# WiFiChristmasStar.net
KiCad netlist of a schematic drawn in EAGLE
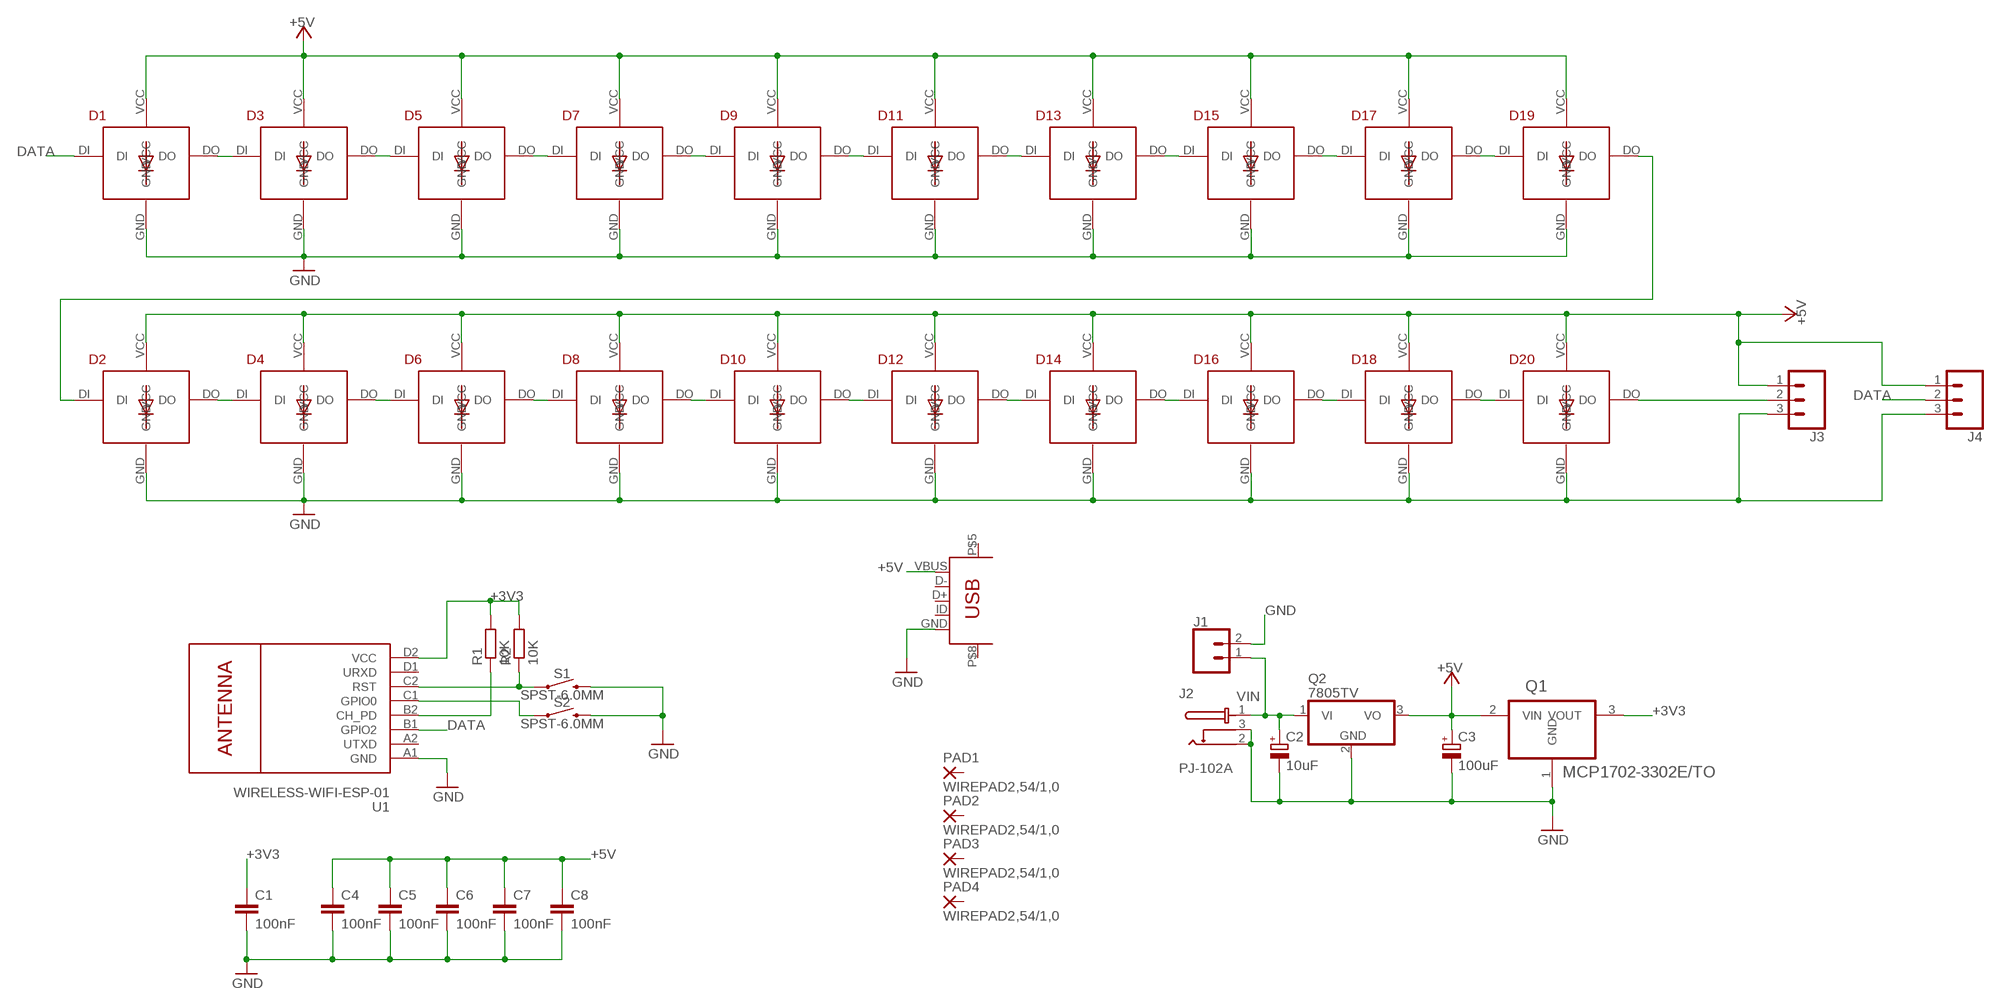
[diagram p0: schematic, sheet 1]

(export (version "E")
  (design (tool "Eeschema 10.0.6"))
  (components
    (comp (ref "C1")
      (value "100nF")
      (footprint "eagle-import:C025-025X050")
      (libsource (lib "eagle-import") (part "C-EU025-025X050"))
    )
    (comp (ref "C2")
      (value "10uF")
      (footprint "eagle-import:E2,5-6")
      (libsource (lib "eagle-import") (part "CPOL-EUE2.5-6"))
    )
    (comp (ref "C3")
      (value "100uF")
      (footprint "eagle-import:E2,5-6")
      (libsource (lib "eagle-import") (part "CPOL-EUE2.5-6"))
    )
    (comp (ref "C4")
      (value "100nF")
      (footprint "eagle-import:C025-025X050")
      (libsource (lib "eagle-import") (part "C-EU025-025X050"))
    )
    (comp (ref "C5")
      (value "100nF")
      (footprint "eagle-import:C025-025X050")
      (libsource (lib "eagle-import") (part "C-EU025-025X050"))
    )
    (comp (ref "C6")
      (value "100nF")
      (footprint "eagle-import:C025-025X050")
      (libsource (lib "eagle-import") (part "C-EU025-025X050"))
    )
    (comp (ref "C7")
      (value "100nF")
      (footprint "eagle-import:C025-025X050")
      (libsource (lib "eagle-import") (part "C-EU025-025X050"))
    )
    (comp (ref "C8")
      (value "100nF")
      (footprint "eagle-import:C025-025X050")
      (libsource (lib "eagle-import") (part "C-EU025-025X050"))
    )
    (comp (ref "CON1")
      (value "MOLEX-548190519-MICROUSB")
      (footprint "eagle-import:MOLEX-548190519")
      (libsource (lib "eagle-import") (part "MOLEX-548190519-MICROUSB"))
    )
    (comp (ref "D1")
      (value "APA-106")
      (footprint "eagle-import:LED5MMRGB")
      (libsource (lib "eagle-import") (part "APA-106"))
    )
    (comp (ref "D2")
      (value "APA-106")
      (footprint "eagle-import:LED5MMRGB")
      (libsource (lib "eagle-import") (part "APA-106"))
    )
    (comp (ref "D3")
      (value "APA-106")
      (footprint "eagle-import:LED5MMRGB")
      (libsource (lib "eagle-import") (part "APA-106"))
    )
    (comp (ref "D4")
      (value "APA-106")
      (footprint "eagle-import:LED5MMRGB")
      (libsource (lib "eagle-import") (part "APA-106"))
    )
    (comp (ref "D5")
      (value "APA-106")
      (footprint "eagle-import:LED5MMRGB")
      (libsource (lib "eagle-import") (part "APA-106"))
    )
    (comp (ref "D6")
      (value "APA-106")
      (footprint "eagle-import:LED5MMRGB")
      (libsource (lib "eagle-import") (part "APA-106"))
    )
    (comp (ref "D7")
      (value "APA-106")
      (footprint "eagle-import:LED5MMRGB")
      (libsource (lib "eagle-import") (part "APA-106"))
    )
    (comp (ref "D8")
      (value "APA-106")
      (footprint "eagle-import:LED5MMRGB")
      (libsource (lib "eagle-import") (part "APA-106"))
    )
    (comp (ref "D9")
      (value "APA-106")
      (footprint "eagle-import:LED5MMRGB")
      (libsource (lib "eagle-import") (part "APA-106"))
    )
    (comp (ref "D10")
      (value "APA-106")
      (footprint "eagle-import:LED5MMRGB")
      (libsource (lib "eagle-import") (part "APA-106"))
    )
    (comp (ref "D11")
      (value "APA-106")
      (footprint "eagle-import:LED5MMRGB")
      (libsource (lib "eagle-import") (part "APA-106"))
    )
    (comp (ref "D12")
      (value "APA-106")
      (footprint "eagle-import:LED5MMRGB")
      (libsource (lib "eagle-import") (part "APA-106"))
    )
    (comp (ref "D13")
      (value "APA-106")
      (footprint "eagle-import:LED5MMRGB")
      (libsource (lib "eagle-import") (part "APA-106"))
    )
    (comp (ref "D14")
      (value "APA-106")
      (footprint "eagle-import:LED5MMRGB")
      (libsource (lib "eagle-import") (part "APA-106"))
    )
    (comp (ref "D15")
      (value "APA-106")
      (footprint "eagle-import:LED5MMRGB")
      (libsource (lib "eagle-import") (part "APA-106"))
    )
    (comp (ref "D16")
      (value "APA-106")
      (footprint "eagle-import:LED5MMRGB")
      (libsource (lib "eagle-import") (part "APA-106"))
    )
    (comp (ref "D17")
      (value "APA-106")
      (footprint "eagle-import:LED5MMRGB")
      (libsource (lib "eagle-import") (part "APA-106"))
    )
    (comp (ref "D18")
      (value "APA-106")
      (footprint "eagle-import:LED5MMRGB")
      (libsource (lib "eagle-import") (part "APA-106"))
    )
    (comp (ref "D19")
      (value "APA-106")
      (footprint "eagle-import:LED5MMRGB")
      (libsource (lib "eagle-import") (part "APA-106"))
    )
    (comp (ref "D20")
      (value "APA-106")
      (footprint "eagle-import:LED5MMRGB")
      (libsource (lib "eagle-import") (part "APA-106"))
    )
    (comp (ref "J1")
      (value "CONN_023.5MM")
      (footprint "eagle-import:SCREWTERMINAL-3.5MM-2")
      (libsource (lib "eagle-import") (part "CONN_023.5MM"))
    )
    (comp (ref "J2")
      (value "PJ-102A")
      (footprint "eagle-import:CUI_PJ-102A")
      (fields (field (name "MANUFACTURER") "CUI inc") (field (name "MF") "CUI"))
      (libsource (lib "eagle-import") (part "PJ-102A"))
    )
    (comp (ref "J3")
      (value "CONN_03SCREW")
      (footprint "eagle-import:SCREWTERMINAL-3.5MM-3")
      (libsource (lib "eagle-import") (part "CONN_03SCREW"))
    )
    (comp (ref "J4")
      (value "CONN_03SCREW")
      (footprint "eagle-import:SCREWTERMINAL-3.5MM-3")
      (libsource (lib "eagle-import") (part "CONN_03SCREW"))
    )
    (comp (ref "PAD1")
      (value "WIREPAD2,54/1,0")
      (footprint "eagle-import:2,54_1,0")
      (libsource (lib "eagle-import") (part "WIREPAD2,54/1,0"))
    )
    (comp (ref "PAD2")
      (value "WIREPAD2,54/1,0")
      (footprint "eagle-import:2,54_1,0")
      (libsource (lib "eagle-import") (part "WIREPAD2,54/1,0"))
    )
    (comp (ref "PAD3")
      (value "WIREPAD2,54/1,0")
      (footprint "eagle-import:2,54_1,0")
      (libsource (lib "eagle-import") (part "WIREPAD2,54/1,0"))
    )
    (comp (ref "PAD4")
      (value "WIREPAD2,54/1,0")
      (footprint "eagle-import:2,54_1,0")
      (libsource (lib "eagle-import") (part "WIREPAD2,54/1,0"))
    )
    (comp (ref "Q1")
      (value "MCP1702-3302E/TO")
      (footprint "eagle-import:TO127P254X533-3")
      (libsource (lib "eagle-import") (part "MCP1702-3302E/TO"))
    )
    (comp (ref "Q2")
      (value "7805TV")
      (footprint "eagle-import:TO220V")
      (libsource (lib "eagle-import") (part "78TV05"))
    )
    (comp (ref "R1")
      (value "10K")
      (footprint "eagle-import:0204_7")
      (libsource (lib "eagle-import") (part "R-EU_0204/7"))
    )
    (comp (ref "R2")
      (value "10K")
      (footprint "eagle-import:0204_7")
      (libsource (lib "eagle-import") (part "R-EU_0204/7"))
    )
    (comp (ref "S1")
      (value "SPST-6.0MM")
      (footprint "eagle-import:TACTILE_SWITCH_PTH_6.0MM")
      (libsource (lib "eagle-import") (part "MOMENTARY-SWITCH-SPST-PTH-6.0MM"))
    )
    (comp (ref "S2")
      (value "SPST-6.0MM")
      (footprint "eagle-import:TACTILE_SWITCH_PTH_6.0MM")
      (libsource (lib "eagle-import") (part "MOMENTARY-SWITCH-SPST-PTH-6.0MM"))
    )
    (comp (ref "U1")
      (value "WIRELESS-WIFI-ESP-01")
      (footprint "eagle-import:WIRELESS-WIFI-ESP-01")
      (libsource (lib "eagle-import") (part "WIRELESS-WIFI-ESP-01"))
    )
  )
  (nets
    (net (code "1") (name "+5V") (class "Default")
      (node (ref "C3") (pin "+") (pinfunction "+_+") (pintype "passive"))
      (node (ref "C4") (pin "1") (pinfunction "1_1") (pintype "passive"))
      (node (ref "C5") (pin "1") (pinfunction "1_1") (pintype "passive"))
      (node (ref "C6") (pin "1") (pinfunction "1_1") (pintype "passive"))
      (node (ref "C7") (pin "1") (pinfunction "1_1") (pintype "passive"))
      (node (ref "C8") (pin "1") (pinfunction "1_1") (pintype "passive"))
      (node (ref "CON1") (pin "VBUS") (pinfunction "VBUS_VBUS") (pintype "bidirectional"))
      (node (ref "D1") (pin "VCC") (pinfunction "VCC_VCC") (pintype "bidirectional"))
      (node (ref "D10") (pin "VCC") (pinfunction "VCC_VCC") (pintype "bidirectional"))
      (node (ref "D11") (pin "VCC") (pinfunction "VCC_VCC") (pintype "bidirectional"))
      (node (ref "D12") (pin "VCC") (pinfunction "VCC_VCC") (pintype "bidirectional"))
      (node (ref "D13") (pin "VCC") (pinfunction "VCC_VCC") (pintype "bidirectional"))
      (node (ref "D14") (pin "VCC") (pinfunction "VCC_VCC") (pintype "bidirectional"))
      (node (ref "D15") (pin "VCC") (pinfunction "VCC_VCC") (pintype "bidirectional"))
      (node (ref "D16") (pin "VCC") (pinfunction "VCC_VCC") (pintype "bidirectional"))
      (node (ref "D17") (pin "VCC") (pinfunction "VCC_VCC") (pintype "bidirectional"))
      (node (ref "D18") (pin "VCC") (pinfunction "VCC_VCC") (pintype "bidirectional"))
      (node (ref "D19") (pin "VCC") (pinfunction "VCC_VCC") (pintype "bidirectional"))
      (node (ref "D2") (pin "VCC") (pinfunction "VCC_VCC") (pintype "bidirectional"))
      (node (ref "D20") (pin "VCC") (pinfunction "VCC_VCC") (pintype "bidirectional"))
      (node (ref "D3") (pin "VCC") (pinfunction "VCC_VCC") (pintype "bidirectional"))
      (node (ref "D4") (pin "VCC") (pinfunction "VCC_VCC") (pintype "bidirectional"))
      (node (ref "D5") (pin "VCC") (pinfunction "VCC_VCC") (pintype "bidirectional"))
      (node (ref "D6") (pin "VCC") (pinfunction "VCC_VCC") (pintype "bidirectional"))
      (node (ref "D7") (pin "VCC") (pinfunction "VCC_VCC") (pintype "bidirectional"))
      (node (ref "D8") (pin "VCC") (pinfunction "VCC_VCC") (pintype "bidirectional"))
      (node (ref "D9") (pin "VCC") (pinfunction "VCC_VCC") (pintype "bidirectional"))
      (node (ref "J3") (pin "1") (pinfunction "1_1") (pintype "passive"))
      (node (ref "J4") (pin "1") (pinfunction "1_1") (pintype "passive"))
      (node (ref "Q1") (pin "2") (pinfunction "VIN_2") (pintype "input"))
      (node (ref "Q2") (pin "3") (pinfunction "VO_3") (pintype "passive"))
    )
    (net (code "2") (name "/+3V3") (class "Default")
      (node (ref "C1") (pin "1") (pinfunction "1_1") (pintype "passive"))
      (node (ref "Q1") (pin "3") (pinfunction "VOUT_3") (pintype "output"))
      (node (ref "R1") (pin "2") (pinfunction "2_2") (pintype "passive"))
      (node (ref "R2") (pin "2") (pinfunction "2_2") (pintype "passive"))
      (node (ref "U1") (pin "D2") (pinfunction "VCC_D2") (pintype "power_in"))
    )
    (net (code "3") (name "/DATA") (class "Default")
      (node (ref "D1") (pin "DI") (pinfunction "DI_DI") (pintype "bidirectional"))
      (node (ref "J4") (pin "2") (pinfunction "2_2") (pintype "passive"))
      (node (ref "U1") (pin "B1") (pinfunction "GPIO2_B1") (pintype "bidirectional"))
    )
    (net (code "4") (name "/VIN") (class "Default")
      (node (ref "C2") (pin "+") (pinfunction "+_+") (pintype "passive"))
      (node (ref "J1") (pin "1") (pinfunction "1_1") (pintype "passive"))
      (node (ref "J2") (pin "1") (pinfunction "1_1") (pintype "power_in"))
      (node (ref "Q2") (pin "1") (pinfunction "VI_1") (pintype "input"))
    )
    (net (code "5") (name "GND") (class "Default")
      (node (ref "C1") (pin "2") (pinfunction "2_2") (pintype "passive"))
      (node (ref "C2") (pin "-") (pinfunction "-_-") (pintype "passive"))
      (node (ref "C3") (pin "-") (pinfunction "-_-") (pintype "passive"))
      (node (ref "C4") (pin "2") (pinfunction "2_2") (pintype "passive"))
      (node (ref "C5") (pin "2") (pinfunction "2_2") (pintype "passive"))
      (node (ref "C6") (pin "2") (pinfunction "2_2") (pintype "passive"))
      (node (ref "C7") (pin "2") (pinfunction "2_2") (pintype "passive"))
      (node (ref "C8") (pin "2") (pinfunction "2_2") (pintype "passive"))
      (node (ref "CON1") (pin "GND") (pinfunction "GND_GND") (pintype "bidirectional"))
      (node (ref "D1") (pin "GND") (pinfunction "GND_GND") (pintype "bidirectional"))
      (node (ref "D10") (pin "GND") (pinfunction "GND_GND") (pintype "bidirectional"))
      (node (ref "D11") (pin "GND") (pinfunction "GND_GND") (pintype "bidirectional"))
      (node (ref "D12") (pin "GND") (pinfunction "GND_GND") (pintype "bidirectional"))
      (node (ref "D13") (pin "GND") (pinfunction "GND_GND") (pintype "bidirectional"))
      (node (ref "D14") (pin "GND") (pinfunction "GND_GND") (pintype "bidirectional"))
      (node (ref "D15") (pin "GND") (pinfunction "GND_GND") (pintype "bidirectional"))
      (node (ref "D16") (pin "GND") (pinfunction "GND_GND") (pintype "bidirectional"))
      (node (ref "D17") (pin "GND") (pinfunction "GND_GND") (pintype "bidirectional"))
      (node (ref "D18") (pin "GND") (pinfunction "GND_GND") (pintype "bidirectional"))
      (node (ref "D19") (pin "GND") (pinfunction "GND_GND") (pintype "bidirectional"))
      (node (ref "D2") (pin "GND") (pinfunction "GND_GND") (pintype "bidirectional"))
      (node (ref "D20") (pin "GND") (pinfunction "GND_GND") (pintype "bidirectional"))
      (node (ref "D3") (pin "GND") (pinfunction "GND_GND") (pintype "bidirectional"))
      (node (ref "D4") (pin "GND") (pinfunction "GND_GND") (pintype "bidirectional"))
      (node (ref "D5") (pin "GND") (pinfunction "GND_GND") (pintype "bidirectional"))
      (node (ref "D6") (pin "GND") (pinfunction "GND_GND") (pintype "bidirectional"))
      (node (ref "D7") (pin "GND") (pinfunction "GND_GND") (pintype "bidirectional"))
      (node (ref "D8") (pin "GND") (pinfunction "GND_GND") (pintype "bidirectional"))
      (node (ref "D9") (pin "GND") (pinfunction "GND_GND") (pintype "bidirectional"))
      (node (ref "J1") (pin "2") (pinfunction "2_2") (pintype "passive"))
      (node (ref "J2") (pin "2") (pinfunction "2_2") (pintype "power_in"))
      (node (ref "J2") (pin "3") (pinfunction "3_3") (pintype "power_in"))
      (node (ref "J3") (pin "3") (pinfunction "3_3") (pintype "passive"))
      (node (ref "J4") (pin "3") (pinfunction "3_3") (pintype "passive"))
      (node (ref "Q1") (pin "1") (pinfunction "GND_1") (pintype "passive"))
      (node (ref "Q2") (pin "2") (pinfunction "GND_2") (pintype "passive"))
      (node (ref "S1") (pin "3") (pinfunction "2_3") (pintype "passive"))
      (node (ref "S2") (pin "3") (pinfunction "2_3") (pintype "passive"))
      (node (ref "U1") (pin "A1") (pinfunction "GND_A1") (pintype "power_in"))
    )
    (net (code "6") (name "Net-(D1-PadDO)") (class "Default")
      (node (ref "D1") (pin "DO") (pinfunction "DO_DO") (pintype "bidirectional"))
      (node (ref "D3") (pin "DI") (pinfunction "DI_DI") (pintype "bidirectional"))
    )
    (net (code "7") (name "Net-(D2-PadDO)") (class "Default")
      (node (ref "D2") (pin "DO") (pinfunction "DO_DO") (pintype "bidirectional"))
      (node (ref "D4") (pin "DI") (pinfunction "DI_DI") (pintype "bidirectional"))
    )
    (net (code "8") (name "Net-(D3-PadDO)") (class "Default")
      (node (ref "D3") (pin "DO") (pinfunction "DO_DO") (pintype "bidirectional"))
      (node (ref "D5") (pin "DI") (pinfunction "DI_DI") (pintype "bidirectional"))
    )
    (net (code "9") (name "Net-(D4-PadDO)") (class "Default")
      (node (ref "D4") (pin "DO") (pinfunction "DO_DO") (pintype "bidirectional"))
      (node (ref "D6") (pin "DI") (pinfunction "DI_DI") (pintype "bidirectional"))
    )
    (net (code "10") (name "Net-(D5-PadDO)") (class "Default")
      (node (ref "D5") (pin "DO") (pinfunction "DO_DO") (pintype "bidirectional"))
      (node (ref "D7") (pin "DI") (pinfunction "DI_DI") (pintype "bidirectional"))
    )
    (net (code "11") (name "Net-(D6-PadDO)") (class "Default")
      (node (ref "D6") (pin "DO") (pinfunction "DO_DO") (pintype "bidirectional"))
      (node (ref "D8") (pin "DI") (pinfunction "DI_DI") (pintype "bidirectional"))
    )
    (net (code "12") (name "Net-(D7-PadDO)") (class "Default")
      (node (ref "D7") (pin "DO") (pinfunction "DO_DO") (pintype "bidirectional"))
      (node (ref "D9") (pin "DI") (pinfunction "DI_DI") (pintype "bidirectional"))
    )
    (net (code "13") (name "Net-(D10-PadDI)") (class "Default")
      (node (ref "D10") (pin "DI") (pinfunction "DI_DI") (pintype "bidirectional"))
      (node (ref "D8") (pin "DO") (pinfunction "DO_DO") (pintype "bidirectional"))
    )
    (net (code "14") (name "Net-(D10-PadDO)") (class "Default")
      (node (ref "D10") (pin "DO") (pinfunction "DO_DO") (pintype "bidirectional"))
      (node (ref "D12") (pin "DI") (pinfunction "DI_DI") (pintype "bidirectional"))
    )
    (net (code "15") (name "Net-(D11-PadDI)") (class "Default")
      (node (ref "D11") (pin "DI") (pinfunction "DI_DI") (pintype "bidirectional"))
      (node (ref "D9") (pin "DO") (pinfunction "DO_DO") (pintype "bidirectional"))
    )
    (net (code "16") (name "Net-(D11-PadDO)") (class "Default")
      (node (ref "D11") (pin "DO") (pinfunction "DO_DO") (pintype "bidirectional"))
      (node (ref "D13") (pin "DI") (pinfunction "DI_DI") (pintype "bidirectional"))
    )
    (net (code "17") (name "Net-(D12-PadDO)") (class "Default")
      (node (ref "D12") (pin "DO") (pinfunction "DO_DO") (pintype "bidirectional"))
      (node (ref "D14") (pin "DI") (pinfunction "DI_DI") (pintype "bidirectional"))
    )
    (net (code "18") (name "Net-(D13-PadDO)") (class "Default")
      (node (ref "D13") (pin "DO") (pinfunction "DO_DO") (pintype "bidirectional"))
      (node (ref "D15") (pin "DI") (pinfunction "DI_DI") (pintype "bidirectional"))
    )
    (net (code "19") (name "Net-(D14-PadDO)") (class "Default")
      (node (ref "D14") (pin "DO") (pinfunction "DO_DO") (pintype "bidirectional"))
      (node (ref "D16") (pin "DI") (pinfunction "DI_DI") (pintype "bidirectional"))
    )
    (net (code "20") (name "Net-(D15-PadDO)") (class "Default")
      (node (ref "D15") (pin "DO") (pinfunction "DO_DO") (pintype "bidirectional"))
      (node (ref "D17") (pin "DI") (pinfunction "DI_DI") (pintype "bidirectional"))
    )
    (net (code "21") (name "Net-(D16-PadDO)") (class "Default")
      (node (ref "D16") (pin "DO") (pinfunction "DO_DO") (pintype "bidirectional"))
      (node (ref "D18") (pin "DI") (pinfunction "DI_DI") (pintype "bidirectional"))
    )
    (net (code "22") (name "Net-(D17-PadDO)") (class "Default")
      (node (ref "D17") (pin "DO") (pinfunction "DO_DO") (pintype "bidirectional"))
      (node (ref "D19") (pin "DI") (pinfunction "DI_DI") (pintype "bidirectional"))
    )
    (net (code "23") (name "Net-(D18-PadDO)") (class "Default")
      (node (ref "D18") (pin "DO") (pinfunction "DO_DO") (pintype "bidirectional"))
      (node (ref "D20") (pin "DI") (pinfunction "DI_DI") (pintype "bidirectional"))
    )
    (net (code "24") (name "Net-(D19-PadDO)") (class "Default")
      (node (ref "D19") (pin "DO") (pinfunction "DO_DO") (pintype "bidirectional"))
      (node (ref "D2") (pin "DI") (pinfunction "DI_DI") (pintype "bidirectional"))
    )
    (net (code "25") (name "Net-(D20-PadDO)") (class "Default")
      (node (ref "D20") (pin "DO") (pinfunction "DO_DO") (pintype "bidirectional"))
      (node (ref "J3") (pin "2") (pinfunction "2_2") (pintype "passive"))
    )
    (net (code "26") (name "Net-(U1-CH_PD)") (class "Default")
      (node (ref "R1") (pin "1") (pinfunction "1_1") (pintype "passive"))
      (node (ref "U1") (pin "B2") (pinfunction "CH_PD_B2") (pintype "bidirectional"))
    )
    (net (code "27") (name "Net-(U1-GPIO0)") (class "Default")
      (node (ref "S2") (pin "1") (pinfunction "1_1") (pintype "passive"))
      (node (ref "U1") (pin "C1") (pinfunction "GPIO0_C1") (pintype "bidirectional"))
    )
    (net (code "28") (name "Net-(U1-RST)") (class "Default")
      (node (ref "R2") (pin "1") (pinfunction "1_1") (pintype "passive"))
      (node (ref "S1") (pin "1") (pinfunction "1_1") (pintype "passive"))
      (node (ref "U1") (pin "C2") (pinfunction "RST_C2") (pintype "bidirectional"))
    )
    (net (code "29") (name "unconnected-(CON1-MTN2-PadP$5)") (class "Default")
      (node (ref "CON1") (pin "P$5") (pinfunction "MTN2_P$5") (pintype "bidirectional"))
    )
    (net (code "30") (name "unconnected-(CON1-MTN4-PadP$8)") (class "Default")
      (node (ref "CON1") (pin "P$8") (pinfunction "MTN4_P$8") (pintype "bidirectional"))
    )
    (net (code "31") (name "unconnected-(CON1-PadD+)") (class "Default")
      (node (ref "CON1") (pin "D+") (pinfunction "D+_D+") (pintype "bidirectional"))
    )
    (net (code "32") (name "unconnected-(CON1-PadD-)") (class "Default")
      (node (ref "CON1") (pin "D-") (pinfunction "D-_D-") (pintype "bidirectional"))
    )
    (net (code "33") (name "unconnected-(CON1-PadID)") (class "Default")
      (node (ref "CON1") (pin "ID") (pinfunction "ID_ID") (pintype "bidirectional"))
    )
    (net (code "34") (name "unconnected-(PAD1-P-Pad1)") (class "Default")
      (node (ref "PAD1") (pin "1") (pinfunction "P_1") (pintype "passive"))
    )
    (net (code "35") (name "unconnected-(PAD2-P-Pad1)") (class "Default")
      (node (ref "PAD2") (pin "1") (pinfunction "P_1") (pintype "passive"))
    )
    (net (code "36") (name "unconnected-(PAD3-P-Pad1)") (class "Default")
      (node (ref "PAD3") (pin "1") (pinfunction "P_1") (pintype "passive"))
    )
    (net (code "37") (name "unconnected-(PAD4-P-Pad1)") (class "Default")
      (node (ref "PAD4") (pin "1") (pinfunction "P_1") (pintype "passive"))
    )
    (net (code "38") (name "unconnected-(U1-URXD-PadD1)") (class "Default")
      (node (ref "U1") (pin "D1") (pinfunction "URXD_D1") (pintype "bidirectional"))
    )
    (net (code "39") (name "unconnected-(U1-UTXD-PadA2)") (class "Default")
      (node (ref "U1") (pin "A2") (pinfunction "UTXD_A2") (pintype "bidirectional"))
    )
  )
)
